# RS232.net
KiCad netlist of a schematic drawn in Altium Designer
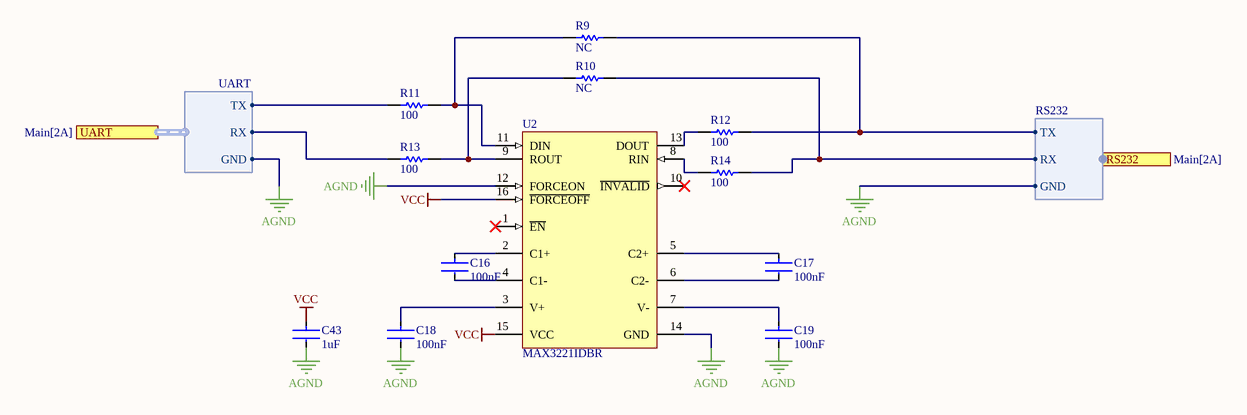
[diagram p0: RS232.SchDoc]

(export (version "E")
  (design (tool "Eeschema 10.0.6"))
  (components
    (comp (ref "C16")
      (value "100nF")
      (footprint "Hosein_PCB_Lib_SMD:CAP-0603")
      (description "Chip Multilayer Ceramic Capacitors for General Purpose, 0603")
      (fields (field (name "VOLTAGE") "6.3V") (field (name "TOLERANCE") "20%"))
      (libsource (lib "Hosein_PCB_Lib") (part "CAP-Ceramic"))
    )
    (comp (ref "C17")
      (value "100nF")
      (footprint "Hosein_PCB_Lib_SMD:CAP-0603")
      (description "Chip Multilayer Ceramic Capacitors for General Purpose, 0603")
      (fields (field (name "VOLTAGE") "6.3V") (field (name "TOLERANCE") "20%"))
      (libsource (lib "Hosein_PCB_Lib") (part "CAP-Ceramic"))
    )
    (comp (ref "C18")
      (value "100nF")
      (footprint "Hosein_PCB_Lib_SMD:CAP-0603")
      (description "Chip Multilayer Ceramic Capacitors for General Purpose, 0603")
      (fields (field (name "VOLTAGE") "6.3V") (field (name "TOLERANCE") "20%"))
      (libsource (lib "Hosein_PCB_Lib") (part "CAP-Ceramic"))
    )
    (comp (ref "C19")
      (value "100nF")
      (footprint "Hosein_PCB_Lib_SMD:CAP-0603")
      (description "Chip Multilayer Ceramic Capacitors for General Purpose, 0603")
      (fields (field (name "VOLTAGE") "6.3V") (field (name "TOLERANCE") "20%"))
      (libsource (lib "Hosein_PCB_Lib") (part "CAP-Ceramic"))
    )
    (comp (ref "C43")
      (value "1uF")
      (footprint "Hosein_PCB_Lib_SMD:CAP-0603")
      (description "Chip Multilayer Ceramic Capacitors for General Purpose, 0603")
      (fields (field (name "VOLTAGE") "6.3V") (field (name "TOLERANCE") "20%"))
      (libsource (lib "Hosein_PCB_Lib") (part "CAP-Ceramic"))
    )
    (comp (ref "R9")
      (value "NC")
      (footprint "Hosein_PCB_Lib_SMD:RES-0603")
      (description "Chip Resistor")
      (fields (field (name "MANUFACTURER") "Vishay Semiconductor"))
      (libsource (lib "Hosein_PCB_Lib") (part "RES_SMD"))
    )
    (comp (ref "R10")
      (value "NC")
      (footprint "Hosein_PCB_Lib_SMD:RES-0603")
      (description "Chip Resistor")
      (fields (field (name "MANUFACTURER") "Vishay Semiconductor"))
      (libsource (lib "Hosein_PCB_Lib") (part "RES_SMD"))
    )
    (comp (ref "R11")
      (value "100")
      (footprint "Hosein_PCB_Lib_SMD:RES-0603")
      (description "Chip Resistor")
      (fields (field (name "MANUFACTURER") "Vishay Semiconductor"))
      (libsource (lib "Hosein_PCB_Lib") (part "RES_SMD"))
    )
    (comp (ref "R12")
      (value "100")
      (footprint "Hosein_PCB_Lib_SMD:RES-0603")
      (description "Chip Resistor")
      (fields (field (name "MANUFACTURER") "Vishay Semiconductor"))
      (libsource (lib "Hosein_PCB_Lib") (part "RES_SMD"))
    )
    (comp (ref "R13")
      (value "100")
      (footprint "Hosein_PCB_Lib_SMD:RES-0603")
      (description "Chip Resistor")
      (fields (field (name "MANUFACTURER") "Vishay Semiconductor"))
      (libsource (lib "Hosein_PCB_Lib") (part "RES_SMD"))
    )
    (comp (ref "R14")
      (value "100")
      (footprint "Hosein_PCB_Lib_SMD:RES-0603")
      (description "Chip Resistor")
      (fields (field (name "MANUFACTURER") "Vishay Semiconductor"))
      (libsource (lib "Hosein_PCB_Lib") (part "RES_SMD"))
    )
    (comp (ref "U2")
      (value "MAX3221IDBR")
      (footprint "DB0016A_M")
      (libsource (lib "Altium Content Vault") (part "TI-MAX3221-SSOP_DB-16"))
    )
  )
  (nets
    (net (code "5") (name "AGND") (class "Default")
      (node (ref "C18") (pin "2") (pinfunction "2_2") (pintype "passive"))
      (node (ref "C19") (pin "2") (pinfunction "2_2") (pintype "passive"))
      (node (ref "C43") (pin "2") (pinfunction "2_2") (pintype "passive"))
      (node (ref "U2") (pin "12") (pinfunction "FORCEON_12") (pintype "input"))
      (node (ref "U2") (pin "14") (pinfunction "GND_14") (pintype "power_in"))
    )
    (net (code "6") (name "Net-(R10-Pad2)") (class "Default")
      (node (ref "R10") (pin "2") (pinfunction "2_2") (pintype "passive"))
      (node (ref "R14") (pin "2") (pinfunction "2_2") (pintype "passive"))
    )
    (net (code "7") (name "Net-(R12-Pad2)") (class "Default")
      (node (ref "R12") (pin "2") (pinfunction "2_2") (pintype "passive"))
      (node (ref "R9") (pin "2") (pinfunction "2_2") (pintype "passive"))
    )
    (net (code "8") (name "Net-(U2-C1+)") (class "Default")
      (node (ref "C16") (pin "1") (pinfunction "1_1") (pintype "passive"))
      (node (ref "U2") (pin "2") (pinfunction "C1+_2") (pintype "passive"))
    )
    (net (code "9") (name "Net-(U2-C1-)") (class "Default")
      (node (ref "C16") (pin "2") (pinfunction "2_2") (pintype "passive"))
      (node (ref "U2") (pin "4") (pinfunction "C1-_4") (pintype "passive"))
    )
    (net (code "10") (name "Net-(U2-C2+)") (class "Default")
      (node (ref "C17") (pin "1") (pinfunction "1_1") (pintype "passive"))
      (node (ref "U2") (pin "5") (pinfunction "C2+_5") (pintype "passive"))
    )
    (net (code "11") (name "Net-(U2-C2-)") (class "Default")
      (node (ref "C17") (pin "2") (pinfunction "2_2") (pintype "passive"))
      (node (ref "U2") (pin "6") (pinfunction "C2-_6") (pintype "passive"))
    )
    (net (code "12") (name "Net-(U2-DIN)") (class "Default")
      (node (ref "R11") (pin "2") (pinfunction "2_2") (pintype "passive"))
      (node (ref "R9") (pin "1") (pinfunction "1_1") (pintype "passive"))
      (node (ref "U2") (pin "11") (pinfunction "DIN_11") (pintype "input"))
    )
    (net (code "13") (name "Net-(U2-DOUT)") (class "Default")
      (node (ref "R12") (pin "1") (pinfunction "1_1") (pintype "passive"))
      (node (ref "U2") (pin "13") (pinfunction "DOUT_13") (pintype "tri_state"))
    )
    (net (code "14") (name "Net-(U2-RIN)") (class "Default")
      (node (ref "R14") (pin "1") (pinfunction "1_1") (pintype "passive"))
      (node (ref "U2") (pin "8") (pinfunction "RIN_8") (pintype "input"))
    )
    (net (code "15") (name "Net-(U2-ROUT)") (class "Default")
      (node (ref "R10") (pin "1") (pinfunction "1_1") (pintype "passive"))
      (node (ref "R13") (pin "2") (pinfunction "2_2") (pintype "passive"))
      (node (ref "U2") (pin "9") (pinfunction "ROUT_9") (pintype "tri_state"))
    )
    (net (code "16") (name "Net-(U2-V+)") (class "Default")
      (node (ref "C18") (pin "1") (pinfunction "1_1") (pintype "passive"))
      (node (ref "U2") (pin "3") (pinfunction "V+_3") (pintype "power_in"))
    )
    (net (code "17") (name "Net-(U2-V-)") (class "Default")
      (node (ref "C19") (pin "1") (pinfunction "1_1") (pintype "passive"))
      (node (ref "U2") (pin "7") (pinfunction "V-_7") (pintype "power_in"))
    )
    (net (code "18") (name "VCC") (class "Default")
      (node (ref "C43") (pin "1") (pinfunction "1_1") (pintype "passive"))
      (node (ref "U2") (pin "15") (pinfunction "VCC_15") (pintype "power_in"))
      (node (ref "U2") (pin "16") (pinfunction "~{FORCEOFF}_16") (pintype "input"))
    )
    (net (code "19") (name "unconnected-(R11-Pad1)") (class "Default")
      (node (ref "R11") (pin "1") (pinfunction "1_1") (pintype "passive"))
    )
    (net (code "20") (name "unconnected-(R13-Pad1)") (class "Default")
      (node (ref "R13") (pin "1") (pinfunction "1_1") (pintype "passive"))
    )
    (net (code "21") (name "unconnected-(U2-~{EN}-Pad1)") (class "Default")
      (node (ref "U2") (pin "1") (pinfunction "~{EN}_1") (pintype "input+no_connect"))
    )
    (net (code "22") (name "unconnected-(U2-~{INVALID}-Pad10)") (class "Default")
      (node (ref "U2") (pin "10") (pinfunction "~{INVALID}_10") (pintype "output+no_connect"))
    )
  )
)
